# Hindi_character.net
KiCad netlist of a schematic drawn in EAGLE
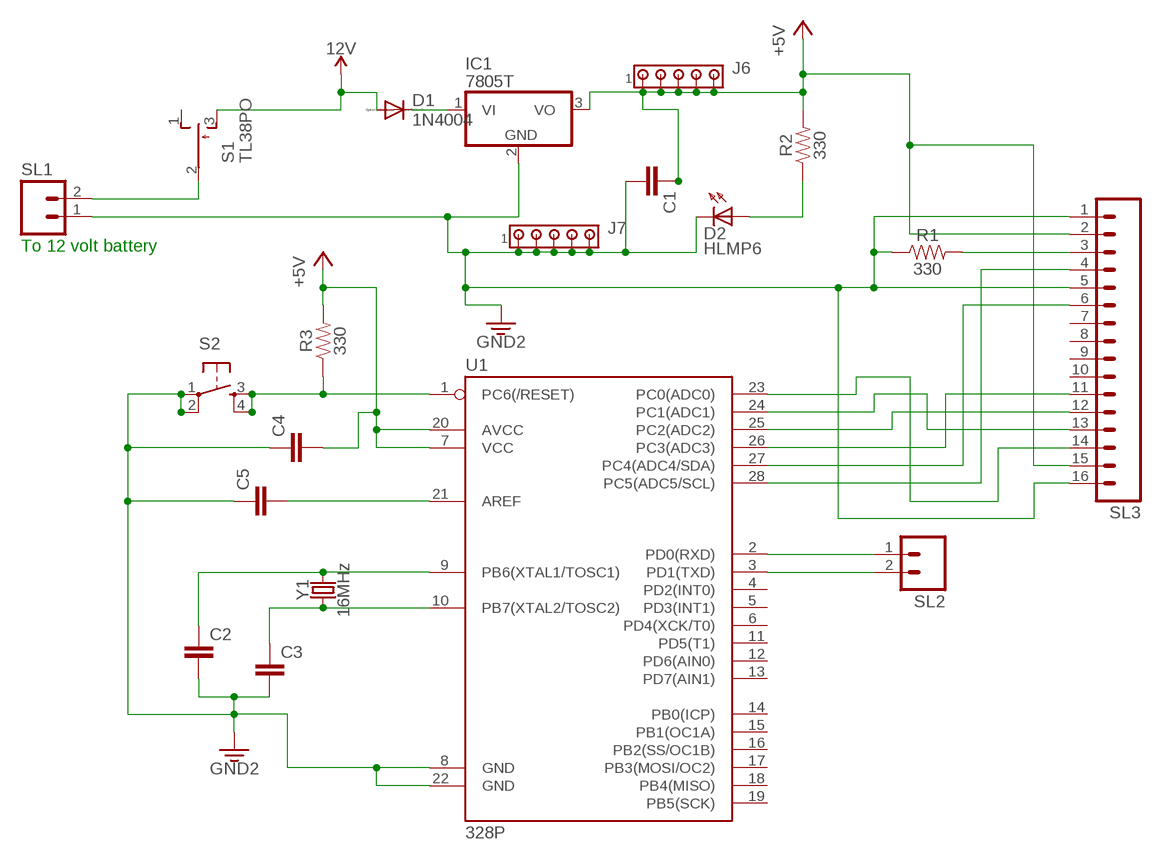
[diagram p0: schematic, sheet 1]

(export (version "E")
  (design (tool "Eeschema 10.0.6"))
  (components
    (comp (ref "C1")
      (value "C5/2.5")
      (footprint "eagle-import:C5B2.5")
      (libsource (lib "eagle-import") (part "C5/2.5"))
    )
    (comp (ref "C2")
      (value "C5/2.5")
      (footprint "eagle-import:C5B2.5")
      (libsource (lib "eagle-import") (part "C5/2.5"))
    )
    (comp (ref "C3")
      (value "C5/2.5")
      (footprint "eagle-import:C5B2.5")
      (libsource (lib "eagle-import") (part "C5/2.5"))
    )
    (comp (ref "C4")
      (value "C5/2.5")
      (footprint "eagle-import:C5B2.5")
      (libsource (lib "eagle-import") (part "C5/2.5"))
    )
    (comp (ref "C5")
      (value "C5/2.5")
      (footprint "eagle-import:C5B2.5")
      (libsource (lib "eagle-import") (part "C5/2.5"))
    )
    (comp (ref "D1")
      (value "1N4004")
      (footprint "eagle-import:DO41-10")
      (libsource (lib "eagle-import") (part "1N4004"))
    )
    (comp (ref "D2")
      (value "HLMP6")
      (footprint "eagle-import:HLMP6")
      (fields (field (name "MF") "AGILENT TECHNOLOGIES") (field (name "MPN") "HLMP-6500"))
      (libsource (lib "eagle-import") (part "HLMP6"))
    )
    (comp (ref "IC1")
      (value "7805T")
      (footprint "eagle-import:TO220H")
      (libsource (lib "eagle-import") (part "78T05"))
    )
    (comp (ref "J6")
      (value "MTA05-100")
      (footprint "eagle-import:10X05MTA")
      (libsource (lib "eagle-import") (part "MTA05-100"))
    )
    (comp (ref "J7")
      (value "MTA05-100")
      (footprint "eagle-import:10X05MTA")
      (libsource (lib "eagle-import") (part "MTA05-100"))
    )
    (comp (ref "R1")
      (value "330")
      (footprint "eagle-import:AXIAL-0.3")
      (libsource (lib "eagle-import") (part "330OHM-HORIZ-1/10W-5%"))
    )
    (comp (ref "R2")
      (value "330")
      (footprint "eagle-import:AXIAL-0.3")
      (libsource (lib "eagle-import") (part "330OHM-HORIZ-1/10W-5%"))
    )
    (comp (ref "R3")
      (value "330")
      (footprint "eagle-import:AXIAL-0.3")
      (libsource (lib "eagle-import") (part "330OHM-HORIZ-1/10W-5%"))
    )
    (comp (ref "S1")
      (value "TL38PO")
      (footprint "eagle-import:TL3XPO")
      (libsource (lib "eagle-import") (part "TL38PO"))
    )
    (comp (ref "S2")
      (value "TAC_SWITCHPTH")
      (footprint "eagle-import:TACTILE-PTH")
      (libsource (lib "eagle-import") (part "TAC_SWITCHPTH"))
    )
    (comp (ref "SL1")
      (value "MA02")
      (footprint "eagle-import:02PA")
      (libsource (lib "eagle-import") (part "MA02"))
    )
    (comp (ref "SL2")
      (value "MA02")
      (footprint "eagle-import:02PA")
      (libsource (lib "eagle-import") (part "MA02"))
    )
    (comp (ref "SL3")
      (value "MA16")
      (footprint "eagle-import:16PA")
      (libsource (lib "eagle-import") (part "MA16"))
    )
    (comp (ref "U1")
      (value "328P")
      (footprint "eagle-import:DIP28")
      (libsource (lib "eagle-import") (part "ATMEGA328P_PDIP"))
    )
    (comp (ref "Y1")
      (value "16MHz")
      (footprint "eagle-import:HC49US")
      (libsource (lib "eagle-import") (part "CRYSTAL-16MHZPTH-HC49US"))
    )
  )
  (nets
    (net (code "1") (name "+5V") (class "Default")
      (node (ref "C1") (pin "1") (pinfunction "1_1") (pintype "passive"))
      (node (ref "C4") (pin "2") (pinfunction "2_2") (pintype "passive"))
      (node (ref "IC1") (pin "3") (pinfunction "VO_3") (pintype "passive"))
      (node (ref "J6") (pin "1") (pinfunction "1_1") (pintype "passive"))
      (node (ref "J6") (pin "2") (pinfunction "2_2") (pintype "passive"))
      (node (ref "J6") (pin "3") (pinfunction "3_3") (pintype "passive"))
      (node (ref "J6") (pin "4") (pinfunction "4_4") (pintype "passive"))
      (node (ref "J6") (pin "5") (pinfunction "5_5") (pintype "passive"))
      (node (ref "R2") (pin "P$2") (pinfunction "2_P$2") (pintype "passive"))
      (node (ref "R3") (pin "P$2") (pinfunction "2_P$2") (pintype "passive"))
      (node (ref "SL3") (pin "15") (pinfunction "15_15") (pintype "passive"))
      (node (ref "SL3") (pin "2") (pinfunction "2_2") (pintype "passive"))
      (node (ref "U1") (pin "20") (pinfunction "AVCC_20") (pintype "bidirectional"))
      (node (ref "U1") (pin "7") (pinfunction "VCC_7") (pintype "bidirectional"))
    )
    (net (code "2") (name "12V") (class "Default")
      (node (ref "D1") (pin "A") (pinfunction "A_A") (pintype "passive"))
      (node (ref "S1") (pin "3") (pinfunction "S_3") (pintype "passive"))
    )
    (net (code "3") (name "GND2") (class "Default")
      (node (ref "C1") (pin "2") (pinfunction "2_2") (pintype "passive"))
      (node (ref "C2") (pin "2") (pinfunction "2_2") (pintype "passive"))
      (node (ref "C3") (pin "2") (pinfunction "2_2") (pintype "passive"))
      (node (ref "C4") (pin "1") (pinfunction "1_1") (pintype "passive"))
      (node (ref "C5") (pin "1") (pinfunction "1_1") (pintype "passive"))
      (node (ref "D2") (pin "K") (pinfunction "K_K") (pintype "passive"))
      (node (ref "IC1") (pin "2") (pinfunction "GND_2") (pintype "passive"))
      (node (ref "J7") (pin "1") (pinfunction "1_1") (pintype "passive"))
      (node (ref "J7") (pin "2") (pinfunction "2_2") (pintype "passive"))
      (node (ref "J7") (pin "3") (pinfunction "3_3") (pintype "passive"))
      (node (ref "J7") (pin "4") (pinfunction "4_4") (pintype "passive"))
      (node (ref "J7") (pin "5") (pinfunction "5_5") (pintype "passive"))
      (node (ref "R1") (pin "P$1") (pinfunction "1_P$1") (pintype "passive"))
      (node (ref "S2") (pin "1") (pinfunction "1_1") (pintype "passive"))
      (node (ref "S2") (pin "2") (pinfunction "2_2") (pintype "passive"))
      (node (ref "SL1") (pin "1") (pinfunction "1_1") (pintype "passive"))
      (node (ref "SL3") (pin "1") (pinfunction "1_1") (pintype "passive"))
      (node (ref "SL3") (pin "16") (pinfunction "16_16") (pintype "passive"))
      (node (ref "SL3") (pin "5") (pinfunction "5_5") (pintype "passive"))
      (node (ref "U1") (pin "22") (pinfunction "GND_22") (pintype "bidirectional"))
      (node (ref "U1") (pin "8") (pinfunction "GND_8") (pintype "bidirectional"))
    )
    (net (code "4") (name "Net-(IC1-VI)") (class "Default")
      (node (ref "D1") (pin "C") (pinfunction "C_C") (pintype "passive"))
      (node (ref "IC1") (pin "1") (pinfunction "VI_1") (pintype "input"))
    )
    (net (code "5") (name "Net-(R1-2)") (class "Default")
      (node (ref "R1") (pin "P$2") (pinfunction "2_P$2") (pintype "passive"))
      (node (ref "SL3") (pin "3") (pinfunction "3_3") (pintype "passive"))
    )
    (net (code "6") (name "Net-(R2-1)") (class "Default")
      (node (ref "D2") (pin "A") (pinfunction "A_A") (pintype "passive"))
      (node (ref "R2") (pin "P$1") (pinfunction "1_P$1") (pintype "passive"))
    )
    (net (code "7") (name "Net-(R3-1)") (class "Default")
      (node (ref "R3") (pin "P$1") (pinfunction "1_P$1") (pintype "passive"))
      (node (ref "S2") (pin "3") (pinfunction "3_3") (pintype "passive"))
      (node (ref "S2") (pin "4") (pinfunction "4_4") (pintype "passive"))
      (node (ref "U1") (pin "1") (pinfunction "PC6(/RESET)_1") (pintype "bidirectional"))
    )
    (net (code "8") (name "Net-(S1-P)") (class "Default")
      (node (ref "S1") (pin "2") (pinfunction "P_2") (pintype "passive"))
      (node (ref "SL1") (pin "2") (pinfunction "2_2") (pintype "passive"))
    )
    (net (code "9") (name "Net-(U1-AREF)") (class "Default")
      (node (ref "C5") (pin "2") (pinfunction "2_2") (pintype "passive"))
      (node (ref "U1") (pin "21") (pinfunction "AREF_21") (pintype "bidirectional"))
    )
    (net (code "10") (name "Net-(U1-PB6(XTAL1{slash}TOSC1))") (class "Default")
      (node (ref "C2") (pin "1") (pinfunction "1_1") (pintype "passive"))
      (node (ref "U1") (pin "9") (pinfunction "PB6(XTAL1/TOSC1)_9") (pintype "bidirectional"))
      (node (ref "Y1") (pin "2") (pinfunction "2_2") (pintype "passive"))
    )
    (net (code "11") (name "Net-(U1-PB7(XTAL2{slash}TOSC2))") (class "Default")
      (node (ref "C3") (pin "1") (pinfunction "1_1") (pintype "passive"))
      (node (ref "U1") (pin "10") (pinfunction "PB7(XTAL2/TOSC2)_10") (pintype "bidirectional"))
      (node (ref "Y1") (pin "1") (pinfunction "1_1") (pintype "passive"))
    )
    (net (code "12") (name "Net-(U1-PC0(ADC0))") (class "Default")
      (node (ref "SL3") (pin "14") (pinfunction "14_14") (pintype "passive"))
      (node (ref "U1") (pin "23") (pinfunction "PC0(ADC0)_23") (pintype "bidirectional"))
    )
    (net (code "13") (name "Net-(U1-PC1(ADC1))") (class "Default")
      (node (ref "SL3") (pin "13") (pinfunction "13_13") (pintype "passive"))
      (node (ref "U1") (pin "24") (pinfunction "PC1(ADC1)_24") (pintype "bidirectional"))
    )
    (net (code "14") (name "Net-(U1-PC2(ADC2))") (class "Default")
      (node (ref "SL3") (pin "12") (pinfunction "12_12") (pintype "passive"))
      (node (ref "U1") (pin "25") (pinfunction "PC2(ADC2)_25") (pintype "bidirectional"))
    )
    (net (code "15") (name "Net-(U1-PC3(ADC3))") (class "Default")
      (node (ref "SL3") (pin "11") (pinfunction "11_11") (pintype "passive"))
      (node (ref "U1") (pin "26") (pinfunction "PC3(ADC3)_26") (pintype "bidirectional"))
    )
    (net (code "16") (name "Net-(U1-PC4(ADC4{slash}SDA))") (class "Default")
      (node (ref "SL3") (pin "6") (pinfunction "6_6") (pintype "passive"))
      (node (ref "U1") (pin "27") (pinfunction "PC4(ADC4/SDA)_27") (pintype "bidirectional"))
    )
    (net (code "17") (name "Net-(U1-PC5(ADC5{slash}SCL))") (class "Default")
      (node (ref "SL3") (pin "4") (pinfunction "4_4") (pintype "passive"))
      (node (ref "U1") (pin "28") (pinfunction "PC5(ADC5/SCL)_28") (pintype "bidirectional"))
    )
    (net (code "18") (name "Net-(U1-PD0(RXD))") (class "Default")
      (node (ref "SL2") (pin "1") (pinfunction "1_1") (pintype "passive"))
      (node (ref "U1") (pin "2") (pinfunction "PD0(RXD)_2") (pintype "bidirectional"))
    )
    (net (code "19") (name "Net-(U1-PD1(TXD))") (class "Default")
      (node (ref "SL2") (pin "2") (pinfunction "2_2") (pintype "passive"))
      (node (ref "U1") (pin "3") (pinfunction "PD1(TXD)_3") (pintype "bidirectional"))
    )
    (net (code "20") (name "unconnected-(S1-O-Pad1)") (class "Default")
      (node (ref "S1") (pin "1") (pinfunction "O_1") (pintype "passive"))
    )
    (net (code "21") (name "unconnected-(SL3-Pad7)") (class "Default")
      (node (ref "SL3") (pin "7") (pinfunction "7_7") (pintype "passive"))
    )
    (net (code "22") (name "unconnected-(SL3-Pad8)") (class "Default")
      (node (ref "SL3") (pin "8") (pinfunction "8_8") (pintype "passive"))
    )
    (net (code "23") (name "unconnected-(SL3-Pad9)") (class "Default")
      (node (ref "SL3") (pin "9") (pinfunction "9_9") (pintype "passive"))
    )
    (net (code "24") (name "unconnected-(SL3-Pad10)") (class "Default")
      (node (ref "SL3") (pin "10") (pinfunction "10_10") (pintype "passive"))
    )
    (net (code "25") (name "unconnected-(U1-PB0(ICP)-Pad14)") (class "Default")
      (node (ref "U1") (pin "14") (pinfunction "PB0(ICP)_14") (pintype "bidirectional"))
    )
    (net (code "26") (name "unconnected-(U1-PB1(OC1A)-Pad15)") (class "Default")
      (node (ref "U1") (pin "15") (pinfunction "PB1(OC1A)_15") (pintype "bidirectional"))
    )
    (net (code "27") (name "unconnected-(U1-PB2(SS{slash}OC1B)-Pad16)") (class "Default")
      (node (ref "U1") (pin "16") (pinfunction "PB2(SS/OC1B)_16") (pintype "bidirectional"))
    )
    (net (code "28") (name "unconnected-(U1-PB3(MOSI{slash}OC2)-Pad17)") (class "Default")
      (node (ref "U1") (pin "17") (pinfunction "PB3(MOSI/OC2)_17") (pintype "bidirectional"))
    )
    (net (code "29") (name "unconnected-(U1-PB4(MISO)-Pad18)") (class "Default")
      (node (ref "U1") (pin "18") (pinfunction "PB4(MISO)_18") (pintype "bidirectional"))
    )
    (net (code "30") (name "unconnected-(U1-PB5(SCK)-Pad19)") (class "Default")
      (node (ref "U1") (pin "19") (pinfunction "PB5(SCK)_19") (pintype "bidirectional"))
    )
    (net (code "31") (name "unconnected-(U1-PD2(INT0)-Pad4)") (class "Default")
      (node (ref "U1") (pin "4") (pinfunction "PD2(INT0)_4") (pintype "bidirectional"))
    )
    (net (code "32") (name "unconnected-(U1-PD3(INT1)-Pad5)") (class "Default")
      (node (ref "U1") (pin "5") (pinfunction "PD3(INT1)_5") (pintype "bidirectional"))
    )
    (net (code "33") (name "unconnected-(U1-PD4(XCK{slash}T0)-Pad6)") (class "Default")
      (node (ref "U1") (pin "6") (pinfunction "PD4(XCK/T0)_6") (pintype "bidirectional"))
    )
    (net (code "34") (name "unconnected-(U1-PD5(T1)-Pad11)") (class "Default")
      (node (ref "U1") (pin "11") (pinfunction "PD5(T1)_11") (pintype "bidirectional"))
    )
    (net (code "35") (name "unconnected-(U1-PD6(AIN0)-Pad12)") (class "Default")
      (node (ref "U1") (pin "12") (pinfunction "PD6(AIN0)_12") (pintype "bidirectional"))
    )
    (net (code "36") (name "unconnected-(U1-PD7(AIN1)-Pad13)") (class "Default")
      (node (ref "U1") (pin "13") (pinfunction "PD7(AIN1)_13") (pintype "bidirectional"))
    )
  )
)
